# Y-babies_--_PicAxe_v_1_4.net
KiCad netlist of a schematic drawn in EAGLE
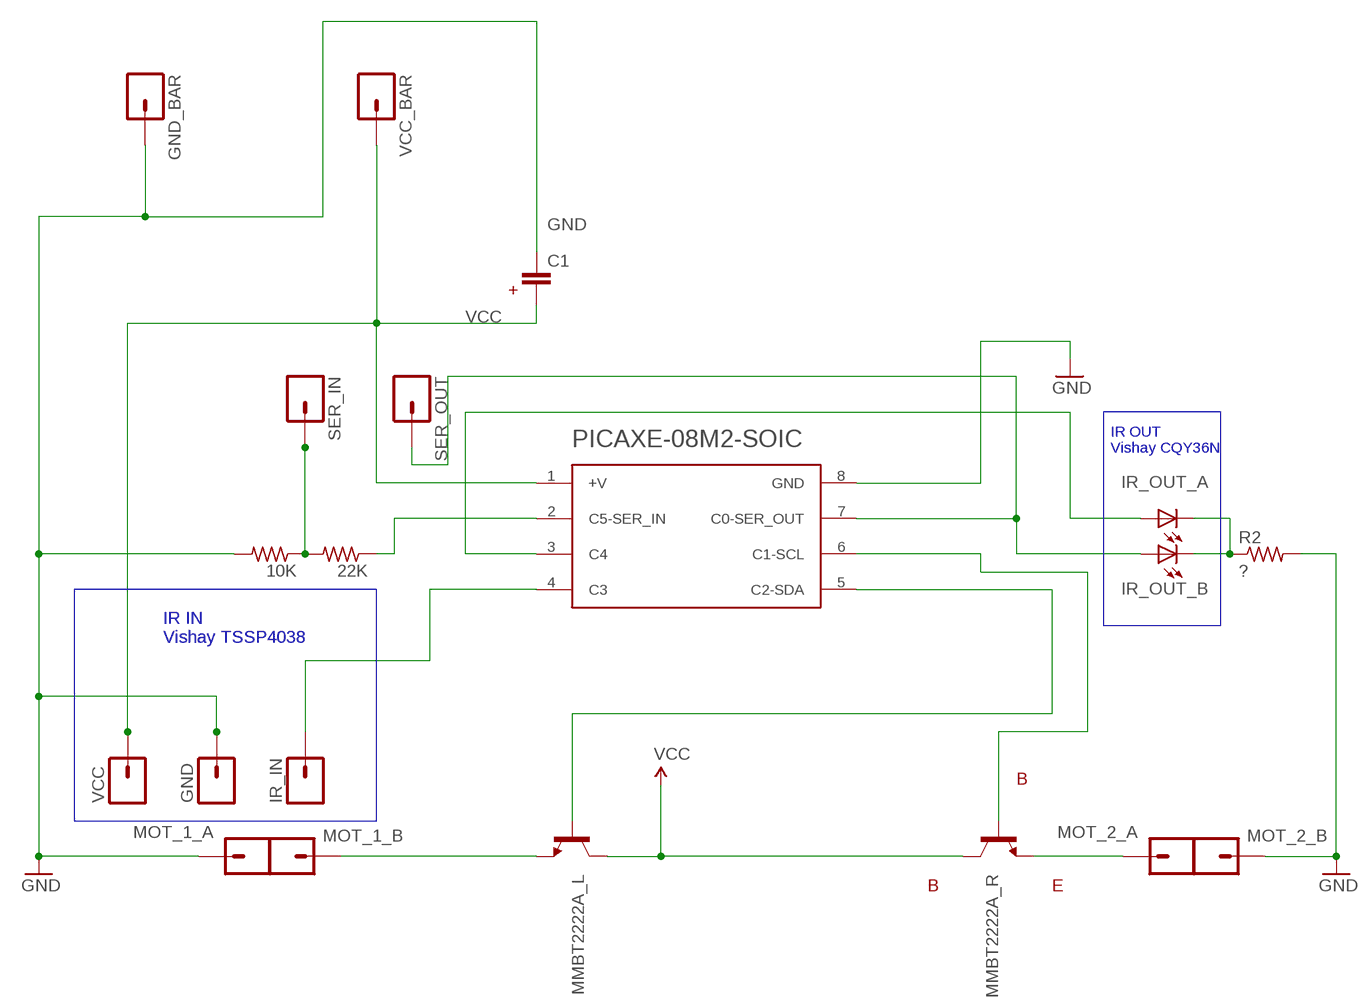
[diagram p0: schematic, sheet 1]

(export (version "E")
  (design (tool "Eeschema 10.0.6"))
  (components
    (comp (ref "10K")
      (value "R-US_R0402")
      (footprint "eagle-import:R0402")
      (libsource (lib "eagle-import") (part "R-US_R0402"))
    )
    (comp (ref "22K")
      (value "R-US_R0402")
      (footprint "eagle-import:R0402")
      (libsource (lib "eagle-import") (part "R-US_R0402"))
    )
    (comp (ref "C1")
      (value "CAPPTH1")
      (footprint "eagle-import:CAP-PTH-5MM")
      (libsource (lib "eagle-import") (part "CAPPTH1"))
    )
    (comp (ref "GND")
      (value "M01PTH")
      (footprint "eagle-import:1X01")
      (libsource (lib "eagle-import") (part "M01PTH"))
    )
    (comp (ref "GND_BAR")
      (value "M01PTH")
      (footprint "eagle-import:1X01")
      (libsource (lib "eagle-import") (part "M01PTH"))
    )
    (comp (ref "IR_IN")
      (value "M01PTH")
      (footprint "eagle-import:1X01")
      (libsource (lib "eagle-import") (part "M01PTH"))
    )
    (comp (ref "IR_OUT_A")
      (value "LED3MM")
      (footprint "eagle-import:LED3MM")
      (libsource (lib "eagle-import") (part "LED3MM"))
    )
    (comp (ref "IR_OUT_B")
      (value "LED3MM")
      (footprint "eagle-import:LED3MM")
      (libsource (lib "eagle-import") (part "LED3MM"))
    )
    (comp (ref "MMBT2222A_L")
      (value "TRANSISTOR_NPNSOT23")
      (footprint "eagle-import:SOT23")
      (libsource (lib "eagle-import") (part "TRANSISTOR_NPNSOT23"))
    )
    (comp (ref "MMBT2222A_R")
      (value "TRANSISTOR_NPNSOT23")
      (footprint "eagle-import:SOT23")
      (libsource (lib "eagle-import") (part "TRANSISTOR_NPNSOT23"))
    )
    (comp (ref "MOT_1_A")
      (value "M01SMD-4.5X1.5")
      (footprint "eagle-import:PAD-1.5X4.5")
      (libsource (lib "eagle-import") (part "M01SMD-4.5X1.5"))
    )
    (comp (ref "MOT_1_B")
      (value "M01SMD-4.5X1.5")
      (footprint "eagle-import:PAD-1.5X4.5")
      (libsource (lib "eagle-import") (part "M01SMD-4.5X1.5"))
    )
    (comp (ref "MOT_2_A")
      (value "M01SMD-4.5X1.5")
      (footprint "eagle-import:PAD-1.5X4.5")
      (libsource (lib "eagle-import") (part "M01SMD-4.5X1.5"))
    )
    (comp (ref "MOT_2_B")
      (value "M01SMD-4.5X1.5")
      (footprint "eagle-import:PAD-1.5X4.5")
      (libsource (lib "eagle-import") (part "M01SMD-4.5X1.5"))
    )
    (comp (ref "R2")
      (value "?")
      (footprint "eagle-import:R0402")
      (libsource (lib "eagle-import") (part "R-US_R0402"))
    )
    (comp (ref "SER_IN")
      (value "M01SMD-4.5X1.5")
      (footprint "eagle-import:PAD-1.5X4.5")
      (libsource (lib "eagle-import") (part "M01SMD-4.5X1.5"))
    )
    (comp (ref "SER_OUT")
      (value "M01SMD-4.5X1.5")
      (footprint "eagle-import:PAD-1.5X4.5")
      (libsource (lib "eagle-import") (part "M01SMD-4.5X1.5"))
    )
    (comp (ref "U$1")
      (value "PICAXE-08M2_SOIC")
      (footprint "eagle-import:SOIC8")
      (libsource (lib "eagle-import") (part "PICAXE-08M2_SOIC"))
    )
    (comp (ref "VCC")
      (value "M01PTH")
      (footprint "eagle-import:1X01")
      (libsource (lib "eagle-import") (part "M01PTH"))
    )
    (comp (ref "VCC_BAR")
      (value "M01PTH")
      (footprint "eagle-import:1X01")
      (libsource (lib "eagle-import") (part "M01PTH"))
    )
  )
  (nets
    (net (code "1") (name "GND") (class "Default")
      (node (ref "10K") (pin "2") (pinfunction "2_2") (pintype "passive"))
      (node (ref "C1") (pin "1") (pinfunction "1_1") (pintype "passive"))
      (node (ref "GND") (pin "1") (pinfunction "1_1") (pintype "passive"))
      (node (ref "GND_BAR") (pin "1") (pinfunction "1_1") (pintype "passive"))
      (node (ref "MOT_1_A") (pin "P$1") (pinfunction "1_P$1") (pintype "passive"))
      (node (ref "MOT_2_B") (pin "P$1") (pinfunction "1_P$1") (pintype "passive"))
      (node (ref "R2") (pin "2") (pinfunction "2_2") (pintype "passive"))
      (node (ref "U$1") (pin "8") (pinfunction "GND_8") (pintype "bidirectional"))
    )
    (net (code "2") (name "Net-(IR_OUT_A-C)") (class "Default")
      (node (ref "IR_OUT_A") (pin "K") (pinfunction "C_K") (pintype "passive"))
      (node (ref "IR_OUT_B") (pin "K") (pinfunction "C_K") (pintype "passive"))
      (node (ref "R2") (pin "1") (pinfunction "1_1") (pintype "passive"))
    )
    (net (code "3") (name "Net-(MMBT2222A_L-B)") (class "Default")
      (node (ref "MMBT2222A_L") (pin "1") (pinfunction "B_1") (pintype "passive"))
      (node (ref "U$1") (pin "5") (pinfunction "C2-SDA_5") (pintype "bidirectional"))
    )
    (net (code "4") (name "Net-(MMBT2222A_L-E)") (class "Default")
      (node (ref "MMBT2222A_L") (pin "2") (pinfunction "E_2") (pintype "passive"))
      (node (ref "MOT_1_B") (pin "P$1") (pinfunction "1_P$1") (pintype "passive"))
    )
    (net (code "5") (name "Net-(MMBT2222A_R-B)") (class "Default")
      (node (ref "MMBT2222A_R") (pin "1") (pinfunction "B_1") (pintype "passive"))
      (node (ref "U$1") (pin "6") (pinfunction "C1-SCL_6") (pintype "bidirectional"))
    )
    (net (code "6") (name "Net-(MMBT2222A_R-E)") (class "Default")
      (node (ref "MMBT2222A_R") (pin "2") (pinfunction "E_2") (pintype "passive"))
      (node (ref "MOT_2_A") (pin "P$1") (pinfunction "1_P$1") (pintype "passive"))
    )
    (net (code "7") (name "Net-(SER_IN-1)") (class "Default")
      (node (ref "10K") (pin "1") (pinfunction "1_1") (pintype "passive"))
      (node (ref "22K") (pin "2") (pinfunction "2_2") (pintype "passive"))
      (node (ref "SER_IN") (pin "P$1") (pinfunction "1_P$1") (pintype "passive"))
    )
    (net (code "8") (name "Net-(SER_OUT-1)") (class "Default")
      (node (ref "IR_OUT_B") (pin "A") (pinfunction "A_A") (pintype "passive"))
      (node (ref "SER_OUT") (pin "P$1") (pinfunction "1_P$1") (pintype "passive"))
      (node (ref "U$1") (pin "7") (pinfunction "C0-SER_OUT_7") (pintype "bidirectional"))
    )
    (net (code "9") (name "Net-(U$1-C3)") (class "Default")
      (node (ref "IR_IN") (pin "1") (pinfunction "1_1") (pintype "passive"))
      (node (ref "U$1") (pin "4") (pinfunction "C3_4") (pintype "bidirectional"))
    )
    (net (code "10") (name "Net-(U$1-C4)") (class "Default")
      (node (ref "IR_OUT_A") (pin "A") (pinfunction "A_A") (pintype "passive"))
      (node (ref "U$1") (pin "3") (pinfunction "C4_3") (pintype "bidirectional"))
    )
    (net (code "11") (name "Net-(U$1-C5-SER_IN)") (class "Default")
      (node (ref "22K") (pin "1") (pinfunction "1_1") (pintype "passive"))
      (node (ref "U$1") (pin "2") (pinfunction "C5-SER_IN_2") (pintype "bidirectional"))
    )
    (net (code "12") (name "VCC") (class "Default")
      (node (ref "C1") (pin "2") (pinfunction "2_2") (pintype "passive"))
      (node (ref "MMBT2222A_L") (pin "3") (pinfunction "C_3") (pintype "passive"))
      (node (ref "MMBT2222A_R") (pin "3") (pinfunction "C_3") (pintype "passive"))
      (node (ref "U$1") (pin "1") (pinfunction "+V_1") (pintype "bidirectional"))
      (node (ref "VCC") (pin "1") (pinfunction "1_1") (pintype "passive"))
      (node (ref "VCC_BAR") (pin "1") (pinfunction "1_1") (pintype "passive"))
    )
  )
)
